# V1.net
KiCad netlist of a schematic drawn in EAGLE
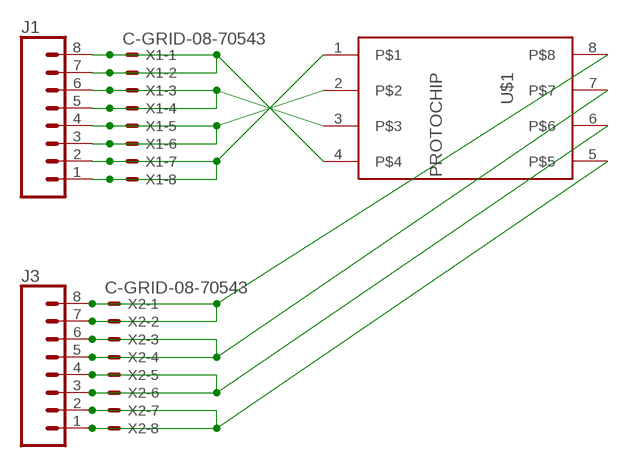
[diagram p0: schematic, sheet 1]

(export (version "E")
  (design (tool "Eeschema 10.0.6"))
  (components
    (comp (ref "J1")
      (value "CONN_08SMD-COMBO-FEMALE")
      (footprint "eagle-import:1X08_SMD_COMBINED")
      (libsource (lib "eagle-import") (part "CONN_08SMD-COMBO-FEMALE"))
    )
    (comp (ref "J3")
      (value "CONN_08SMD-COMBO-FEMALE")
      (footprint "eagle-import:1X08_SMD_COMBINED")
      (libsource (lib "eagle-import") (part "CONN_08SMD-COMBO-FEMALE"))
    )
    (comp (ref "U$1")
      (value "PROTOCHIP")
      (footprint "eagle-import:PROTOCHIP")
      (libsource (lib "eagle-import") (part "PROTOCHIP"))
    )
    (comp (ref "X1")
      (value "C-GRID-08-70543")
      (footprint "eagle-import:70543-08")
      (fields (field (name "MF") "MOLEX"))
      (libsource (lib "eagle-import") (part "C-GRID-08-70543"))
    )
    (comp (ref "X2")
      (value "C-GRID-08-70543")
      (footprint "eagle-import:70543-08")
      (fields (field (name "MF") "MOLEX"))
      (libsource (lib "eagle-import") (part "C-GRID-08-70543"))
    )
  )
  (nets
    (net (code "1") (name "Net-(U$1-P$1)") (class "Default")
      (node (ref "J1") (pin "1") (pinfunction "1_1") (pintype "passive"))
      (node (ref "J1") (pin "2") (pinfunction "2_2") (pintype "passive"))
      (node (ref "U$1") (pin "1") (pinfunction "P$1_1") (pintype "bidirectional"))
      (node (ref "X1") (pin "7") (pinfunction "S_7") (pintype "passive"))
      (node (ref "X1") (pin "8") (pinfunction "S_8") (pintype "passive"))
    )
    (net (code "2") (name "Net-(U$1-P$2)") (class "Default")
      (node (ref "J1") (pin "3") (pinfunction "3_3") (pintype "passive"))
      (node (ref "J1") (pin "4") (pinfunction "4_4") (pintype "passive"))
      (node (ref "U$1") (pin "2") (pinfunction "P$2_2") (pintype "bidirectional"))
      (node (ref "X1") (pin "5") (pinfunction "S_5") (pintype "passive"))
      (node (ref "X1") (pin "6") (pinfunction "S_6") (pintype "passive"))
    )
    (net (code "3") (name "Net-(U$1-P$3)") (class "Default")
      (node (ref "J1") (pin "5") (pinfunction "5_5") (pintype "passive"))
      (node (ref "J1") (pin "6") (pinfunction "6_6") (pintype "passive"))
      (node (ref "U$1") (pin "3") (pinfunction "P$3_3") (pintype "bidirectional"))
      (node (ref "X1") (pin "3") (pinfunction "S_3") (pintype "passive"))
      (node (ref "X1") (pin "4") (pinfunction "S_4") (pintype "passive"))
    )
    (net (code "4") (name "Net-(U$1-P$4)") (class "Default")
      (node (ref "J1") (pin "7") (pinfunction "7_7") (pintype "passive"))
      (node (ref "J1") (pin "8") (pinfunction "8_8") (pintype "passive"))
      (node (ref "U$1") (pin "4") (pinfunction "P$4_4") (pintype "bidirectional"))
      (node (ref "X1") (pin "1") (pinfunction "S_1") (pintype "passive"))
      (node (ref "X1") (pin "2") (pinfunction "S_2") (pintype "passive"))
    )
    (net (code "5") (name "Net-(U$1-P$5)") (class "Default")
      (node (ref "J3") (pin "1") (pinfunction "1_1") (pintype "passive"))
      (node (ref "J3") (pin "2") (pinfunction "2_2") (pintype "passive"))
      (node (ref "U$1") (pin "5") (pinfunction "P$5_5") (pintype "bidirectional"))
      (node (ref "X2") (pin "7") (pinfunction "S_7") (pintype "passive"))
      (node (ref "X2") (pin "8") (pinfunction "S_8") (pintype "passive"))
    )
    (net (code "6") (name "Net-(U$1-P$6)") (class "Default")
      (node (ref "J3") (pin "3") (pinfunction "3_3") (pintype "passive"))
      (node (ref "J3") (pin "4") (pinfunction "4_4") (pintype "passive"))
      (node (ref "U$1") (pin "6") (pinfunction "P$6_6") (pintype "bidirectional"))
      (node (ref "X2") (pin "5") (pinfunction "S_5") (pintype "passive"))
      (node (ref "X2") (pin "6") (pinfunction "S_6") (pintype "passive"))
    )
    (net (code "7") (name "Net-(U$1-P$7)") (class "Default")
      (node (ref "J3") (pin "5") (pinfunction "5_5") (pintype "passive"))
      (node (ref "J3") (pin "6") (pinfunction "6_6") (pintype "passive"))
      (node (ref "U$1") (pin "7") (pinfunction "P$7_7") (pintype "bidirectional"))
      (node (ref "X2") (pin "3") (pinfunction "S_3") (pintype "passive"))
      (node (ref "X2") (pin "4") (pinfunction "S_4") (pintype "passive"))
    )
    (net (code "8") (name "Net-(U$1-P$8)") (class "Default")
      (node (ref "J3") (pin "7") (pinfunction "7_7") (pintype "passive"))
      (node (ref "J3") (pin "8") (pinfunction "8_8") (pintype "passive"))
      (node (ref "U$1") (pin "8") (pinfunction "P$8_8") (pintype "bidirectional"))
      (node (ref "X2") (pin "1") (pinfunction "S_1") (pintype "passive"))
      (node (ref "X2") (pin "2") (pinfunction "S_2") (pintype "passive"))
    )
  )
)
